# Buck_SMPS_Rev2_2022_05_26_A.net
KiCad netlist of a schematic drawn in EAGLE
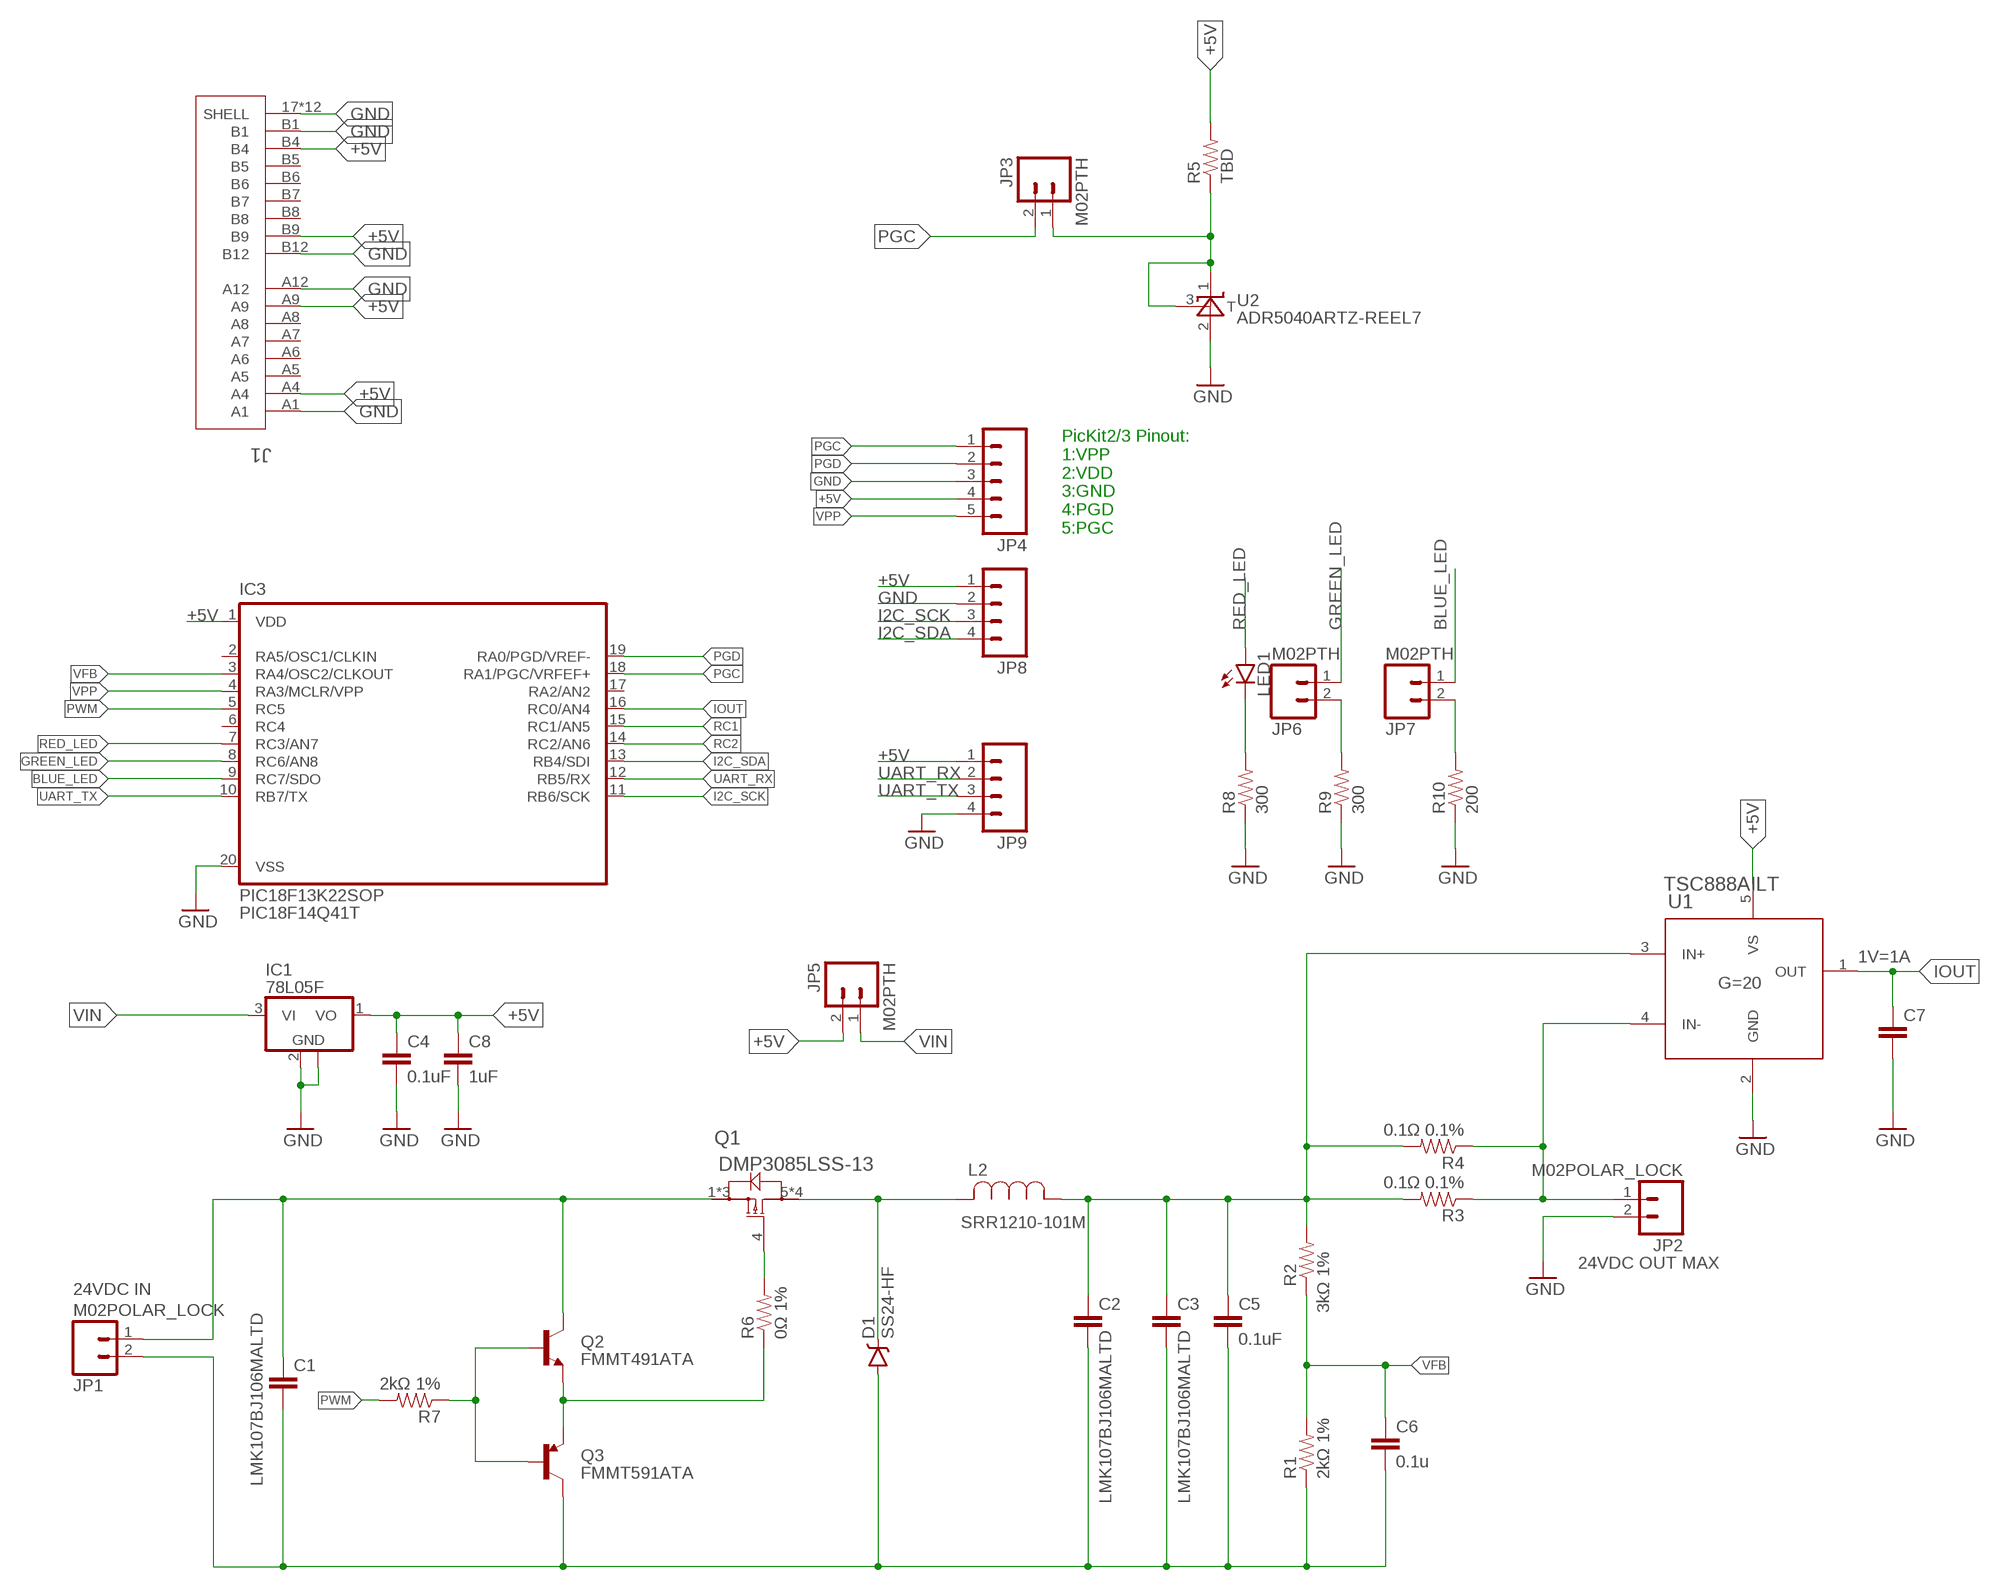
[diagram p0: schematic, sheet 1]

(export (version "E")
  (design (tool "Eeschema 10.0.6"))
  (components
    (comp (ref "C1")
      (value "LMK107BJ106MALTD")
      (footprint "eagle-import:1206")
      (libsource (lib "eagle-import") (part "CAP1206"))
    )
    (comp (ref "C2")
      (value "LMK107BJ106MALTD")
      (footprint "eagle-import:1206")
      (libsource (lib "eagle-import") (part "CAP1206"))
    )
    (comp (ref "C3")
      (value "LMK107BJ106MALTD")
      (footprint "eagle-import:1206")
      (libsource (lib "eagle-import") (part "CAP1206"))
    )
    (comp (ref "C4")
      (value "0.1uF")
      (footprint "eagle-import:1206")
      (libsource (lib "eagle-import") (part "CAP1206"))
    )
    (comp (ref "C5")
      (value "0.1uF")
      (footprint "eagle-import:1206")
      (libsource (lib "eagle-import") (part "CAP1206"))
    )
    (comp (ref "C6")
      (value "0.1u")
      (footprint "eagle-import:0805")
      (libsource (lib "eagle-import") (part "CAP0805"))
    )
    (comp (ref "C7")
      (value "CAP0805")
      (footprint "eagle-import:0805")
      (libsource (lib "eagle-import") (part "CAP0805"))
    )
    (comp (ref "C8")
      (value "1uF")
      (footprint "eagle-import:1206")
      (libsource (lib "eagle-import") (part "CAP1206"))
    )
    (comp (ref "D1")
      (value "SS24-HF")
      (footprint "eagle-import:SMA-DIODE")
      (libsource (lib "eagle-import") (part "DIODE-SCHOTTKY-MBRA140"))
    )
    (comp (ref "IC1")
      (value "78L05F")
      (footprint "eagle-import:SOT89")
      (libsource (lib "eagle-import") (part "78LF05"))
    )
    (comp (ref "IC3")
      (value "PIC18F13K22SOP")
      (footprint "eagle-import:SOP20W")
      (libsource (lib "eagle-import") (part "PIC18F13K22?SOP"))
    )
    (comp (ref "J1")
      (value "USB4085-GF-A")
      (footprint "eagle-import:CONN16_USB4085-GF-A_GCT")
      (fields (field (name "COPYRIGHT") "Copyright (C) 2022 Ultra Librarian. All rights reserved."))
      (libsource (lib "eagle-import") (part "USB4085-GF-A"))
    )
    (comp (ref "JP1")
      (value "M02POLAR_LOCK")
      (footprint "eagle-import:MOLEX-1X2_LOCK")
      (libsource (lib "eagle-import") (part "M02POLAR_LOCK"))
    )
    (comp (ref "JP2")
      (value "M02POLAR_LOCK")
      (footprint "eagle-import:MOLEX-1X2_LOCK")
      (libsource (lib "eagle-import") (part "M02POLAR_LOCK"))
    )
    (comp (ref "JP3")
      (value "M02PTH")
      (footprint "eagle-import:1X02")
      (libsource (lib "eagle-import") (part "M02PTH"))
    )
    (comp (ref "JP4")
      (value "M05PTH_LONGPADS")
      (footprint "eagle-import:1X05_LONGPADS")
      (libsource (lib "eagle-import") (part "M05PTH_LONGPADS"))
    )
    (comp (ref "JP5")
      (value "M02PTH")
      (footprint "eagle-import:1X02")
      (libsource (lib "eagle-import") (part "M02PTH"))
    )
    (comp (ref "JP6")
      (value "M02PTH")
      (footprint "eagle-import:1X02")
      (libsource (lib "eagle-import") (part "M02PTH"))
    )
    (comp (ref "JP7")
      (value "M02PTH")
      (footprint "eagle-import:1X02")
      (libsource (lib "eagle-import") (part "M02PTH"))
    )
    (comp (ref "JP8")
      (value "M04LOCK")
      (footprint "eagle-import:1X04_LOCK")
      (libsource (lib "eagle-import") (part "M04LOCK"))
    )
    (comp (ref "JP9")
      (value "M04LOCK")
      (footprint "eagle-import:1X04_LOCK")
      (libsource (lib "eagle-import") (part "M04LOCK"))
    )
    (comp (ref "L2")
      (value "SRR1210-101M")
      (footprint "eagle-import:IND_BOURNS_SRR1210")
      (fields (field (name "MANUFACTURER_PART_NUMBER") "SRR1210680M"))
      (libsource (lib "eagle-import") (part "SRR1210-680M"))
    )
    (comp (ref "LED1")
      (value "LED1206")
      (footprint "eagle-import:LED-1206")
      (libsource (lib "eagle-import") (part "LED1206"))
    )
    (comp (ref "Q1")
      (value "DMP3085LSS-13")
      (footprint "eagle-import:IC_DMP3085LSS-13_DIO-M")
      (fields (field (name "COPYRIGHT") "Copyright (C) 2021 Ultra Librarian. All rights reserved."))
      (libsource (lib "eagle-import") (part "DMP3085LSS-13IC_DMP3085LSS-13_DIO-M"))
    )
    (comp (ref "Q2")
      (value "FMMT491ATA")
      (footprint "eagle-import:SOT23")
      (libsource (lib "eagle-import") (part "TRANSISTOR_NPNMMBT5088"))
    )
    (comp (ref "Q3")
      (value "FMMT591ATA")
      (footprint "eagle-import:SOT23")
      (libsource (lib "eagle-import") (part "TRANSISTOR_PNPMMBT4403"))
    )
    (comp (ref "R1")
      (value "2kΩ 1%")
      (footprint "eagle-import:1206")
      (libsource (lib "eagle-import") (part "RESISTOR1206"))
    )
    (comp (ref "R2")
      (value "3kΩ 1%")
      (footprint "eagle-import:1206")
      (libsource (lib "eagle-import") (part "RESISTOR1206"))
    )
    (comp (ref "R3")
      (value "0.1Ω 0.1%")
      (footprint "eagle-import:1206")
      (libsource (lib "eagle-import") (part "RESISTOR1206"))
    )
    (comp (ref "R4")
      (value "0.1Ω 0.1%")
      (footprint "eagle-import:1206")
      (libsource (lib "eagle-import") (part "RESISTOR1206"))
    )
    (comp (ref "R5")
      (value "TBD")
      (footprint "eagle-import:1206")
      (libsource (lib "eagle-import") (part "RESISTOR1206"))
    )
    (comp (ref "R6")
      (value "0Ω 1%")
      (footprint "eagle-import:1206")
      (libsource (lib "eagle-import") (part "RESISTOR1206"))
    )
    (comp (ref "R7")
      (value "2kΩ 1%")
      (footprint "eagle-import:1206")
      (libsource (lib "eagle-import") (part "RESISTOR1206"))
    )
    (comp (ref "R8")
      (value "300")
      (footprint "eagle-import:1206")
      (libsource (lib "eagle-import") (part "RESISTOR1206"))
    )
    (comp (ref "R9")
      (value "300")
      (footprint "eagle-import:1206")
      (libsource (lib "eagle-import") (part "RESISTOR1206"))
    )
    (comp (ref "R10")
      (value "200")
      (footprint "eagle-import:1206")
      (libsource (lib "eagle-import") (part "RESISTOR1206"))
    )
    (comp (ref "U1")
      (value "TSC888AILT")
      (footprint "eagle-import:DBV0005A_N")
      (fields (field (name "MANUFACTURER") "Texas Instruments") (field (name "PARTNUMBER") "INA180A1IDBVR"))
      (libsource (lib "eagle-import") (part "INA180A1IDBVR"))
    )
    (comp (ref "U2")
      (value "ADR5040ARTZ-REEL7")
      (footprint "eagle-import:RT_3_ADI")
      (libsource (lib "eagle-import") (part "ADR5040ARTZ-REEL7"))
    )
  )
  (nets
    (net (code "1") (name "+5V") (class "Default")
      (node (ref "C4") (pin "1") (pinfunction "1_1") (pintype "passive"))
      (node (ref "C8") (pin "1") (pinfunction "1_1") (pintype "passive"))
      (node (ref "IC1") (pin "1") (pinfunction "VO_1") (pintype "passive"))
      (node (ref "IC3") (pin "1") (pinfunction "VDD_1") (pintype "power_in"))
      (node (ref "J1") (pin "A4") (pinfunction "A4_A4") (pintype "passive"))
      (node (ref "J1") (pin "A9") (pinfunction "A9_A9") (pintype "passive"))
      (node (ref "J1") (pin "B4") (pinfunction "B4_B4") (pintype "passive"))
      (node (ref "J1") (pin "B9") (pinfunction "B9_B9") (pintype "passive"))
      (node (ref "JP4") (pin "4") (pinfunction "4_4") (pintype "passive"))
      (node (ref "JP5") (pin "2") (pinfunction "2_2") (pintype "passive"))
      (node (ref "JP8") (pin "1") (pinfunction "1_1") (pintype "passive"))
      (node (ref "JP9") (pin "1") (pinfunction "1_1") (pintype "passive"))
      (node (ref "R5") (pin "2") (pinfunction "2_2") (pintype "passive"))
      (node (ref "U1") (pin "5") (pinfunction "VS_5") (pintype "power_in"))
    )
    (net (code "2") (name "BLUE_LED") (class "Default")
      (node (ref "IC3") (pin "9") (pinfunction "RC7/SDO_9") (pintype "bidirectional"))
      (node (ref "JP7") (pin "1") (pinfunction "1_1") (pintype "passive"))
    )
    (net (code "3") (name "GND") (class "Default")
      (node (ref "C1") (pin "2") (pinfunction "2_2") (pintype "passive"))
      (node (ref "C2") (pin "2") (pinfunction "2_2") (pintype "passive"))
      (node (ref "C3") (pin "2") (pinfunction "2_2") (pintype "passive"))
      (node (ref "C4") (pin "2") (pinfunction "2_2") (pintype "passive"))
      (node (ref "C5") (pin "2") (pinfunction "2_2") (pintype "passive"))
      (node (ref "C6") (pin "2") (pinfunction "2_2") (pintype "passive"))
      (node (ref "C7") (pin "2") (pinfunction "2_2") (pintype "passive"))
      (node (ref "C8") (pin "2") (pinfunction "2_2") (pintype "passive"))
      (node (ref "D1") (pin "A") (pinfunction "A_A") (pintype "passive"))
      (node (ref "IC1") (pin "2") (pinfunction "GND_2") (pintype "passive"))
      (node (ref "IC1") (pin "2@1") (pinfunction "GND_2@1") (pintype "passive"))
      (node (ref "IC3") (pin "20") (pinfunction "VSS_20") (pintype "power_in"))
      (node (ref "J1") (pin "17") (pinfunction "SHELL_17") (pintype "passive"))
      (node (ref "J1") (pin "18") (pinfunction "SHELL_18") (pintype "passive"))
      (node (ref "J1") (pin "19") (pinfunction "SHELL_19") (pintype "passive"))
      (node (ref "J1") (pin "20") (pinfunction "SHELL_20") (pintype "passive"))
      (node (ref "J1") (pin "21") (pinfunction "SHELL_21") (pintype "passive"))
      (node (ref "J1") (pin "22") (pinfunction "SHELL_22") (pintype "passive"))
      (node (ref "J1") (pin "23") (pinfunction "SHELL_23") (pintype "passive"))
      (node (ref "J1") (pin "24") (pinfunction "SHELL_24") (pintype "passive"))
      (node (ref "J1") (pin "25") (pinfunction "SHELL_25") (pintype "passive"))
      (node (ref "J1") (pin "26") (pinfunction "SHELL_26") (pintype "passive"))
      (node (ref "J1") (pin "27") (pinfunction "SHELL_27") (pintype "passive"))
      (node (ref "J1") (pin "28") (pinfunction "SHELL_28") (pintype "passive"))
      (node (ref "J1") (pin "A1") (pinfunction "A1_A1") (pintype "passive"))
      (node (ref "J1") (pin "A12") (pinfunction "A12_A12") (pintype "passive"))
      (node (ref "J1") (pin "B1") (pinfunction "B1_B1") (pintype "passive"))
      (node (ref "J1") (pin "B12") (pinfunction "B12_B12") (pintype "passive"))
      (node (ref "JP1") (pin "2") (pinfunction "2_2") (pintype "passive"))
      (node (ref "JP2") (pin "2") (pinfunction "2_2") (pintype "passive"))
      (node (ref "JP4") (pin "3") (pinfunction "3_3") (pintype "passive"))
      (node (ref "JP8") (pin "2") (pinfunction "2_2") (pintype "passive"))
      (node (ref "JP9") (pin "4") (pinfunction "4_4") (pintype "passive"))
      (node (ref "Q3") (pin "3") (pinfunction "C_3") (pintype "passive"))
      (node (ref "R1") (pin "1") (pinfunction "1_1") (pintype "passive"))
      (node (ref "R10") (pin "1") (pinfunction "1_1") (pintype "passive"))
      (node (ref "R8") (pin "1") (pinfunction "1_1") (pintype "passive"))
      (node (ref "R9") (pin "1") (pinfunction "1_1") (pintype "passive"))
      (node (ref "U1") (pin "2") (pinfunction "GND_2") (pintype "power_in"))
      (node (ref "U2") (pin "2") (pinfunction "A_2") (pintype "output"))
    )
    (net (code "4") (name "GREEN_LED") (class "Default")
      (node (ref "IC3") (pin "8") (pinfunction "RC6/AN8_8") (pintype "bidirectional"))
      (node (ref "JP6") (pin "1") (pinfunction "1_1") (pintype "passive"))
    )
    (net (code "5") (name "I2C_SCK") (class "Default")
      (node (ref "IC3") (pin "11") (pinfunction "RB6/SCK_11") (pintype "bidirectional"))
      (node (ref "JP8") (pin "3") (pinfunction "3_3") (pintype "passive"))
    )
    (net (code "6") (name "I2C_SDA") (class "Default")
      (node (ref "IC3") (pin "13") (pinfunction "RB4/SDI_13") (pintype "bidirectional"))
      (node (ref "JP8") (pin "4") (pinfunction "4_4") (pintype "passive"))
    )
    (net (code "7") (name "IOUT") (class "Default")
      (node (ref "C7") (pin "1") (pinfunction "1_1") (pintype "passive"))
      (node (ref "IC3") (pin "16") (pinfunction "RC0/AN4_16") (pintype "bidirectional"))
      (node (ref "U1") (pin "1") (pinfunction "OUT_1") (pintype "output"))
    )
    (net (code "8") (name "Net-(D1-PadC)") (class "Default")
      (node (ref "D1") (pin "C") (pinfunction "C_C") (pintype "passive"))
      (node (ref "L2") (pin "2") (pinfunction "2_2") (pintype "passive"))
      (node (ref "Q1") (pin "5") (pinfunction "D_5") (pintype "passive"))
      (node (ref "Q1") (pin "6") (pinfunction "D_6") (pintype "passive"))
      (node (ref "Q1") (pin "7") (pinfunction "D_7") (pintype "passive"))
      (node (ref "Q1") (pin "8") (pinfunction "D_8") (pintype "passive"))
    )
    (net (code "9") (name "Net-(JP6-Pad2)") (class "Default")
      (node (ref "JP6") (pin "2") (pinfunction "2_2") (pintype "passive"))
      (node (ref "R9") (pin "2") (pinfunction "2_2") (pintype "passive"))
    )
    (net (code "10") (name "Net-(JP7-Pad2)") (class "Default")
      (node (ref "JP7") (pin "2") (pinfunction "2_2") (pintype "passive"))
      (node (ref "R10") (pin "2") (pinfunction "2_2") (pintype "passive"))
    )
    (net (code "11") (name "Net-(LED1-PadC)") (class "Default")
      (node (ref "LED1") (pin "C") (pinfunction "C_C") (pintype "passive"))
      (node (ref "R8") (pin "2") (pinfunction "2_2") (pintype "passive"))
    )
    (net (code "12") (name "Net-(Q1-G)") (class "Default")
      (node (ref "Q1") (pin "4") (pinfunction "G_4") (pintype "passive"))
      (node (ref "R6") (pin "2") (pinfunction "2_2") (pintype "passive"))
    )
    (net (code "13") (name "Net-(Q2-B)") (class "Default")
      (node (ref "Q2") (pin "1") (pinfunction "B_1") (pintype "passive"))
      (node (ref "Q3") (pin "1") (pinfunction "B_1") (pintype "passive"))
      (node (ref "R7") (pin "1") (pinfunction "1_1") (pintype "passive"))
    )
    (net (code "14") (name "Net-(Q2-E)") (class "Default")
      (node (ref "Q2") (pin "2") (pinfunction "E_2") (pintype "passive"))
      (node (ref "Q3") (pin "2") (pinfunction "E_2") (pintype "passive"))
      (node (ref "R6") (pin "1") (pinfunction "1_1") (pintype "passive"))
    )
    (net (code "15") (name "Net-(U1-IN+)") (class "Default")
      (node (ref "C2") (pin "1") (pinfunction "1_1") (pintype "passive"))
      (node (ref "C3") (pin "1") (pinfunction "1_1") (pintype "passive"))
      (node (ref "C5") (pin "1") (pinfunction "1_1") (pintype "passive"))
      (node (ref "L2") (pin "1") (pinfunction "1_1") (pintype "passive"))
      (node (ref "R2") (pin "2") (pinfunction "2_2") (pintype "passive"))
      (node (ref "R3") (pin "2") (pinfunction "2_2") (pintype "passive"))
      (node (ref "R4") (pin "2") (pinfunction "2_2") (pintype "passive"))
      (node (ref "U1") (pin "3") (pinfunction "IN+_3") (pintype "input"))
    )
    (net (code "16") (name "Net-(U1-IN-)") (class "Default")
      (node (ref "JP2") (pin "1") (pinfunction "1_1") (pintype "passive"))
      (node (ref "R3") (pin "1") (pinfunction "1_1") (pintype "passive"))
      (node (ref "R4") (pin "1") (pinfunction "1_1") (pintype "passive"))
      (node (ref "U1") (pin "4") (pinfunction "IN-_4") (pintype "input"))
    )
    (net (code "17") (name "Net-(U2-C)") (class "Default")
      (node (ref "JP3") (pin "1") (pinfunction "1_1") (pintype "passive"))
      (node (ref "R5") (pin "1") (pinfunction "1_1") (pintype "passive"))
      (node (ref "U2") (pin "1") (pinfunction "C_1") (pintype "input"))
      (node (ref "U2") (pin "3") (pinfunction "T_3") (pintype "power_in"))
    )
    (net (code "18") (name "PGC") (class "Default")
      (node (ref "IC3") (pin "18") (pinfunction "RA1/PGC/VRFEF+_18") (pintype "bidirectional"))
      (node (ref "JP3") (pin "2") (pinfunction "2_2") (pintype "passive"))
      (node (ref "JP4") (pin "1") (pinfunction "1_1") (pintype "passive"))
    )
    (net (code "19") (name "PGD") (class "Default")
      (node (ref "IC3") (pin "19") (pinfunction "RA0/PGD/VREF-_19") (pintype "bidirectional"))
      (node (ref "JP4") (pin "2") (pinfunction "2_2") (pintype "passive"))
    )
    (net (code "20") (name "PWM") (class "Default")
      (node (ref "IC3") (pin "5") (pinfunction "RC5_5") (pintype "bidirectional"))
      (node (ref "R7") (pin "2") (pinfunction "2_2") (pintype "passive"))
    )
    (net (code "21") (name "RC1") (class "Default")
      (node (ref "IC3") (pin "15") (pinfunction "RC1/AN5_15") (pintype "bidirectional"))
    )
    (net (code "22") (name "RC2") (class "Default")
      (node (ref "IC3") (pin "14") (pinfunction "RC2/AN6_14") (pintype "bidirectional"))
    )
    (net (code "23") (name "RED_LED") (class "Default")
      (node (ref "IC3") (pin "7") (pinfunction "RC3/AN7_7") (pintype "bidirectional"))
      (node (ref "LED1") (pin "A") (pinfunction "A_A") (pintype "passive"))
    )
    (net (code "24") (name "UART_RX") (class "Default")
      (node (ref "IC3") (pin "12") (pinfunction "RB5/RX_12") (pintype "bidirectional"))
      (node (ref "JP9") (pin "2") (pinfunction "2_2") (pintype "passive"))
    )
    (net (code "25") (name "UART_TX") (class "Default")
      (node (ref "IC3") (pin "10") (pinfunction "RB7/TX_10") (pintype "bidirectional"))
      (node (ref "JP9") (pin "3") (pinfunction "3_3") (pintype "passive"))
    )
    (net (code "26") (name "VFB") (class "Default")
      (node (ref "C6") (pin "1") (pinfunction "1_1") (pintype "passive"))
      (node (ref "IC3") (pin "3") (pinfunction "RA4/OSC2/CLKOUT_3") (pintype "bidirectional"))
      (node (ref "R1") (pin "2") (pinfunction "2_2") (pintype "passive"))
      (node (ref "R2") (pin "1") (pinfunction "1_1") (pintype "passive"))
    )
    (net (code "27") (name "VIN") (class "Default")
      (node (ref "C1") (pin "1") (pinfunction "1_1") (pintype "passive"))
      (node (ref "IC1") (pin "3") (pinfunction "VI_3") (pintype "input"))
      (node (ref "JP1") (pin "1") (pinfunction "1_1") (pintype "passive"))
      (node (ref "JP5") (pin "1") (pinfunction "1_1") (pintype "passive"))
      (node (ref "Q1") (pin "1") (pinfunction "S_1") (pintype "passive"))
      (node (ref "Q1") (pin "2") (pinfunction "S_2") (pintype "passive"))
      (node (ref "Q1") (pin "3") (pinfunction "S_3") (pintype "passive"))
      (node (ref "Q2") (pin "3") (pinfunction "C_3") (pintype "passive"))
    )
    (net (code "28") (name "VPP") (class "Default")
      (node (ref "IC3") (pin "4") (pinfunction "RA3/MCLR/VPP_4") (pintype "bidirectional"))
      (node (ref "JP4") (pin "5") (pinfunction "5_5") (pintype "passive"))
    )
    (net (code "29") (name "unconnected-(IC3-RA2{slash}AN2-Pad17)") (class "Default")
      (node (ref "IC3") (pin "17") (pinfunction "RA2/AN2_17") (pintype "bidirectional"))
    )
    (net (code "30") (name "unconnected-(IC3-RA5{slash}OSC1{slash}CLKIN-Pad2)") (class "Default")
      (node (ref "IC3") (pin "2") (pinfunction "RA5/OSC1/CLKIN_2") (pintype "bidirectional"))
    )
    (net (code "31") (name "unconnected-(IC3-RC4-Pad6)") (class "Default")
      (node (ref "IC3") (pin "6") (pinfunction "RC4_6") (pintype "bidirectional"))
    )
    (net (code "32") (name "unconnected-(J1-PadA5)") (class "Default")
      (node (ref "J1") (pin "A5") (pinfunction "A5_A5") (pintype "passive"))
    )
    (net (code "33") (name "unconnected-(J1-PadA6)") (class "Default")
      (node (ref "J1") (pin "A6") (pinfunction "A6_A6") (pintype "passive"))
    )
    (net (code "34") (name "unconnected-(J1-PadA7)") (class "Default")
      (node (ref "J1") (pin "A7") (pinfunction "A7_A7") (pintype "passive"))
    )
    (net (code "35") (name "unconnected-(J1-PadA8)") (class "Default")
      (node (ref "J1") (pin "A8") (pinfunction "A8_A8") (pintype "passive"))
    )
    (net (code "36") (name "unconnected-(J1-PadB5)") (class "Default")
      (node (ref "J1") (pin "B5") (pinfunction "B5_B5") (pintype "passive"))
    )
    (net (code "37") (name "unconnected-(J1-PadB6)") (class "Default")
      (node (ref "J1") (pin "B6") (pinfunction "B6_B6") (pintype "passive"))
    )
    (net (code "38") (name "unconnected-(J1-PadB7)") (class "Default")
      (node (ref "J1") (pin "B7") (pinfunction "B7_B7") (pintype "passive"))
    )
    (net (code "39") (name "unconnected-(J1-PadB8)") (class "Default")
      (node (ref "J1") (pin "B8") (pinfunction "B8_B8") (pintype "passive"))
    )
  )
)
